# PL-100.net
KiCad netlist of a schematic drawn in EAGLE
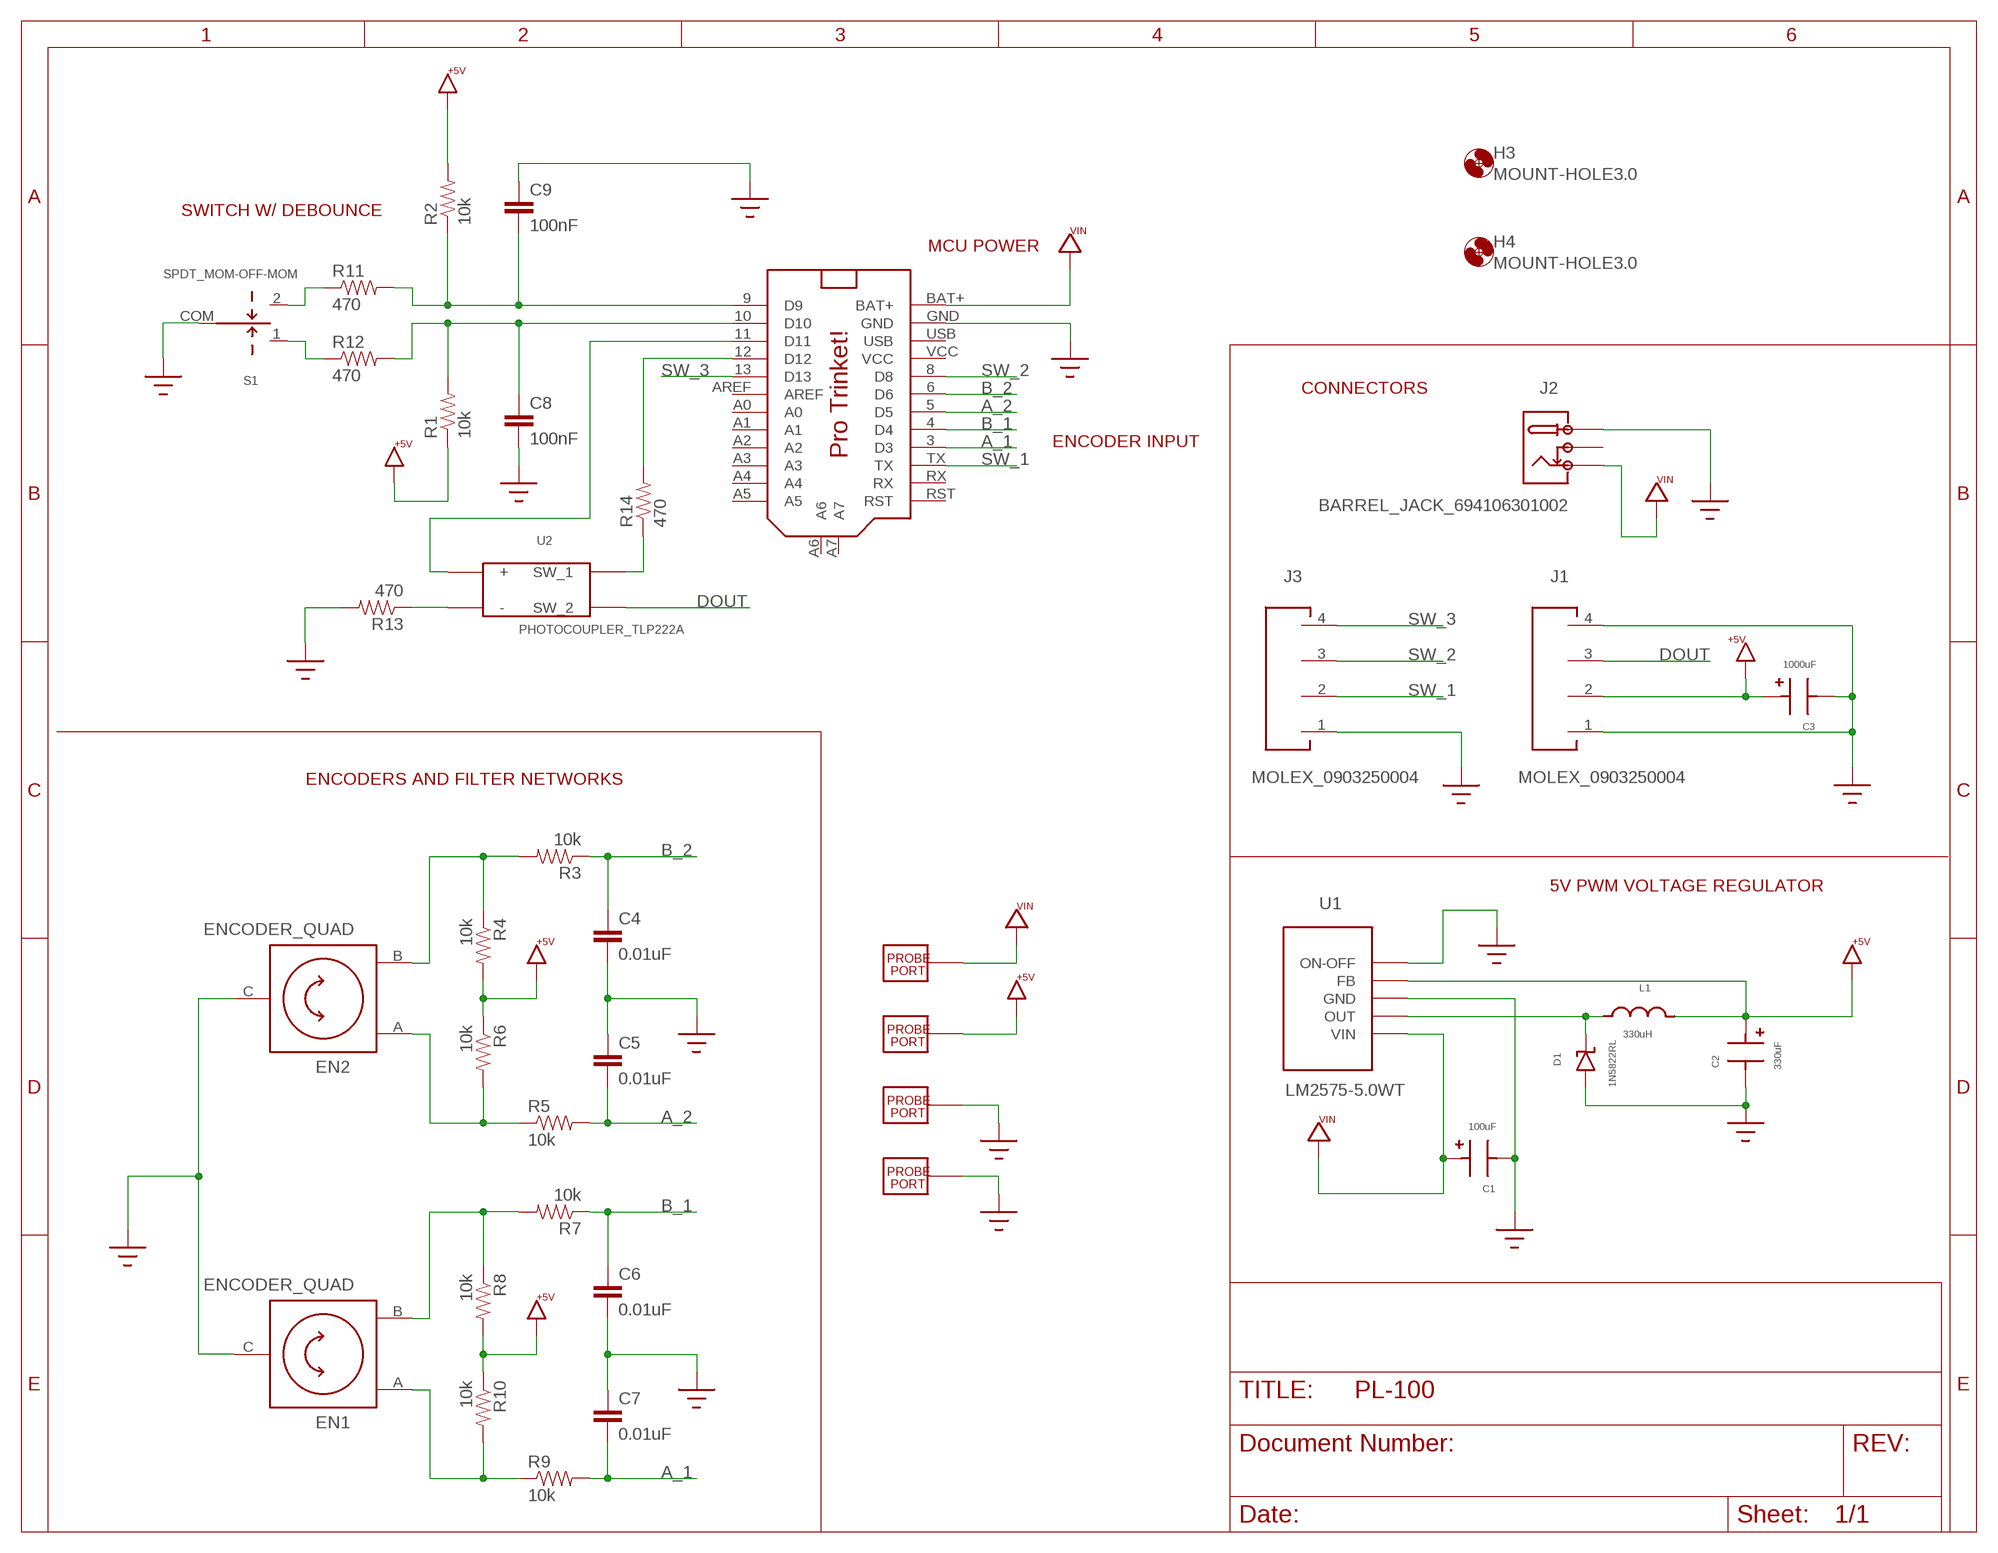
[diagram p0: schematic, sheet 1]

(export (version "E")
  (design (tool "Eeschema 10.0.6"))
  (components
    (comp (ref "+5V")
      (value "PROBE_PORT")
      (footprint "eagle-import:PROBE_PORT")
      (libsource (lib "eagle-import") (part "PROBE_PORT"))
    )
    (comp (ref "C1")
      (value "100uF")
      (footprint "eagle-import:RADIAL_POL_6.3-DIA_2.5-SPACE")
      (libsource (lib "eagle-import") (part "CAP_POL6.3-DIA_2.5-SPACE"))
    )
    (comp (ref "C2")
      (value "330uF")
      (footprint "eagle-import:RADIAL_POL_8-DIA_3.5-SPACE")
      (libsource (lib "eagle-import") (part "CAP_POL8-DIA_3.5-SPACE"))
    )
    (comp (ref "C3")
      (value "1000uF")
      (footprint "eagle-import:RADIAL_POL_10-DIA_5-SPACE")
      (libsource (lib "eagle-import") (part "CAP_POL10-DIA_5-SPACE"))
    )
    (comp (ref "C4")
      (value "0.01uF")
      (footprint "eagle-import:CAP-PTH-SMALLEZ")
      (libsource (lib "eagle-import") (part "CAPEZ"))
    )
    (comp (ref "C5")
      (value "0.01uF")
      (footprint "eagle-import:CAP-PTH-SMALLEZ")
      (libsource (lib "eagle-import") (part "CAPEZ"))
    )
    (comp (ref "C6")
      (value "0.01uF")
      (footprint "eagle-import:CAP-PTH-SMALLEZ")
      (libsource (lib "eagle-import") (part "CAPEZ"))
    )
    (comp (ref "C7")
      (value "0.01uF")
      (footprint "eagle-import:CAP-PTH-SMALLEZ")
      (libsource (lib "eagle-import") (part "CAPEZ"))
    )
    (comp (ref "C8")
      (value "100nF")
      (footprint "eagle-import:CAP-PTH-SMALL")
      (libsource (lib "eagle-import") (part "CAPPTH"))
    )
    (comp (ref "C9")
      (value "100nF")
      (footprint "eagle-import:CAP-PTH-SMALL")
      (libsource (lib "eagle-import") (part "CAPPTH"))
    )
    (comp (ref "D1")
      (value "1N5822RL")
      (footprint "eagle-import:DO-201AD_AXIAL")
      (libsource (lib "eagle-import") (part "DIODE_SHOTTKY"))
    )
    (comp (ref "EN1")
      (value "ENCODER_QUAD")
      (footprint "eagle-import:PEC11R-4015F-N0024")
      (libsource (lib "eagle-import") (part "ENCODER_QUAD"))
    )
    (comp (ref "EN2")
      (value "ENCODER_QUAD")
      (footprint "eagle-import:PEC11R-4015F-N0024")
      (libsource (lib "eagle-import") (part "ENCODER_QUAD"))
    )
    (comp (ref "GND1")
      (value "PROBE_PORT")
      (footprint "eagle-import:PROBE_PORT")
      (libsource (lib "eagle-import") (part "PROBE_PORT"))
    )
    (comp (ref "GND2")
      (value "PROBE_PORT")
      (footprint "eagle-import:PROBE_PORT")
      (libsource (lib "eagle-import") (part "PROBE_PORT"))
    )
    (comp (ref "H3")
      (value "MOUNT-HOLE3.0")
      (footprint "eagle-import:3,0")
      (libsource (lib "eagle-import") (part "MOUNT-HOLE3.0"))
    )
    (comp (ref "H4")
      (value "MOUNT-HOLE3.0")
      (footprint "eagle-import:3,0")
      (libsource (lib "eagle-import") (part "MOUNT-HOLE3.0"))
    )
    (comp (ref "J1")
      (value "MOLEX_0903250004")
      (footprint "eagle-import:0903250004")
      (libsource (lib "eagle-import") (part "MOLEX_0903250004"))
    )
    (comp (ref "J2")
      (value "BARREL_JACK_694106301002")
      (footprint "eagle-import:BARREL_JACK_694106301002")
      (libsource (lib "eagle-import") (part "BARREL_JACK_694106301002"))
    )
    (comp (ref "J3")
      (value "MOLEX_0903250004")
      (footprint "eagle-import:0903250004")
      (libsource (lib "eagle-import") (part "MOLEX_0903250004"))
    )
    (comp (ref "L1")
      (value "330uH")
      (footprint "eagle-import:INDUCT_AXIAL_28-SPACING")
      (libsource (lib "eagle-import") (part "INDUCTOR"))
    )
    (comp (ref "R1")
      (value "10k")
      (footprint "eagle-import:AXIAL-0.4")
      (libsource (lib "eagle-import") (part "RESISTORPTH-1/4W"))
    )
    (comp (ref "R2")
      (value "10k")
      (footprint "eagle-import:AXIAL-0.4")
      (libsource (lib "eagle-import") (part "RESISTORPTH-1/4W"))
    )
    (comp (ref "R3")
      (value "10k")
      (footprint "eagle-import:AXIAL-0.4")
      (libsource (lib "eagle-import") (part "RESISTORPTH-1/4W"))
    )
    (comp (ref "R4")
      (value "10k")
      (footprint "eagle-import:AXIAL-0.4")
      (libsource (lib "eagle-import") (part "RESISTORPTH-1/4W"))
    )
    (comp (ref "R5")
      (value "10k")
      (footprint "eagle-import:AXIAL-0.4")
      (libsource (lib "eagle-import") (part "RESISTORPTH-1/4W"))
    )
    (comp (ref "R6")
      (value "10k")
      (footprint "eagle-import:AXIAL-0.4")
      (libsource (lib "eagle-import") (part "RESISTORPTH-1/4W"))
    )
    (comp (ref "R7")
      (value "10k")
      (footprint "eagle-import:AXIAL-0.4")
      (libsource (lib "eagle-import") (part "RESISTORPTH-1/4W"))
    )
    (comp (ref "R8")
      (value "10k")
      (footprint "eagle-import:AXIAL-0.4")
      (libsource (lib "eagle-import") (part "RESISTORPTH-1/4W"))
    )
    (comp (ref "R9")
      (value "10k")
      (footprint "eagle-import:AXIAL-0.4")
      (libsource (lib "eagle-import") (part "RESISTORPTH-1/4W"))
    )
    (comp (ref "R10")
      (value "10k")
      (footprint "eagle-import:AXIAL-0.4")
      (libsource (lib "eagle-import") (part "RESISTORPTH-1/4W"))
    )
    (comp (ref "R11")
      (value "470")
      (footprint "eagle-import:AXIAL-0.4")
      (libsource (lib "eagle-import") (part "RESISTORPTH-1/4W"))
    )
    (comp (ref "R12")
      (value "470")
      (footprint "eagle-import:AXIAL-0.4")
      (libsource (lib "eagle-import") (part "RESISTORPTH-1/4W"))
    )
    (comp (ref "R13")
      (value "470")
      (footprint "eagle-import:AXIAL-0.4")
      (libsource (lib "eagle-import") (part "RESISTORPTH-1/4W"))
    )
    (comp (ref "R14")
      (value "470")
      (footprint "eagle-import:AXIAL-0.4")
      (libsource (lib "eagle-import") (part "RESISTORPTH-1/4W"))
    )
    (comp (ref "S1")
      (value "SPDT_MOM-OFF-MOM")
      (footprint "eagle-import:100SP4T6B11M2QEH")
      (libsource (lib "eagle-import") (part "SPDT_MOM-OFF-MOM"))
    )
    (comp (ref "U$2")
      (value "PRO_TRINKET")
      (footprint "eagle-import:PROTRINKET")
      (libsource (lib "eagle-import") (part "PRO_TRINKET"))
    )
    (comp (ref "U1")
      (value "LM2575-5.0WT")
      (footprint "eagle-import:TO-220-5")
      (libsource (lib "eagle-import") (part "LM2575-5.0WT"))
    )
    (comp (ref "U2")
      (value "PHOTOCOUPLER_TLP222A")
      (footprint "eagle-import:DIP-4")
      (libsource (lib "eagle-import") (part "PHOTOCOUPLER_TLP222A"))
    )
    (comp (ref "VIN")
      (value "PROBE_PORT")
      (footprint "eagle-import:PROBE_PORT")
      (libsource (lib "eagle-import") (part "PROBE_PORT"))
    )
  )
  (nets
    (net (code "1") (name "+5V") (class "Default")
      (node (ref "+5V") (pin "P$1") (pinfunction "P$1_P$1") (pintype "passive"))
      (node (ref "C2") (pin "+") (pinfunction "+_+") (pintype "passive"))
      (node (ref "C3") (pin "+") (pinfunction "+_+") (pintype "passive"))
      (node (ref "J1") (pin "2") (pinfunction "P$2_2") (pintype "bidirectional"))
      (node (ref "L1") (pin "2") (pinfunction "P$2_2") (pintype "passive"))
      (node (ref "R1") (pin "P$1") (pinfunction "1_P$1") (pintype "passive"))
      (node (ref "R10") (pin "P$1") (pinfunction "1_P$1") (pintype "passive"))
      (node (ref "R2") (pin "P$2") (pinfunction "2_P$2") (pintype "passive"))
      (node (ref "R4") (pin "P$2") (pinfunction "2_P$2") (pintype "passive"))
      (node (ref "R6") (pin "P$1") (pinfunction "1_P$1") (pintype "passive"))
      (node (ref "R8") (pin "P$2") (pinfunction "2_P$2") (pintype "passive"))
      (node (ref "U1") (pin "4") (pinfunction "FB_4") (pintype "input"))
    )
    (net (code "2") (name "/3") (class "Default")
      (node (ref "J2") (pin "3") (pinfunction "3_3") (pintype "power_in"))
    )
    (net (code "3") (name "/A_1") (class "Default")
      (node (ref "C7") (pin "2") (pinfunction "2_2") (pintype "passive"))
      (node (ref "R9") (pin "P$2") (pinfunction "2_P$2") (pintype "passive"))
      (node (ref "U$2") (pin "3") (pinfunction "D3_3") (pintype "bidirectional"))
    )
    (net (code "4") (name "/A_2") (class "Default")
      (node (ref "C5") (pin "2") (pinfunction "2_2") (pintype "passive"))
      (node (ref "R5") (pin "P$2") (pinfunction "2_P$2") (pintype "passive"))
      (node (ref "U$2") (pin "5") (pinfunction "D5_5") (pintype "bidirectional"))
    )
    (net (code "5") (name "/B_1") (class "Default")
      (node (ref "C6") (pin "1") (pinfunction "1_1") (pintype "passive"))
      (node (ref "R7") (pin "P$1") (pinfunction "1_P$1") (pintype "passive"))
      (node (ref "U$2") (pin "4") (pinfunction "D4_4") (pintype "bidirectional"))
    )
    (net (code "6") (name "/B_2") (class "Default")
      (node (ref "C4") (pin "1") (pinfunction "1_1") (pintype "passive"))
      (node (ref "R3") (pin "P$1") (pinfunction "1_P$1") (pintype "passive"))
      (node (ref "U$2") (pin "6") (pinfunction "D6_6") (pintype "bidirectional"))
    )
    (net (code "7") (name "/DOUT") (class "Default")
      (node (ref "J1") (pin "3") (pinfunction "P$3_3") (pintype "passive"))
      (node (ref "U2") (pin "4") (pinfunction "SW_2_4") (pintype "passive"))
    )
    (net (code "8") (name "/SW_1") (class "Default")
      (node (ref "J3") (pin "2") (pinfunction "P$2_2") (pintype "bidirectional"))
      (node (ref "U$2") (pin "TX") (pinfunction "TX_TX") (pintype "bidirectional"))
    )
    (net (code "9") (name "/SW_2") (class "Default")
      (node (ref "J3") (pin "3") (pinfunction "P$3_3") (pintype "passive"))
      (node (ref "U$2") (pin "8") (pinfunction "D8_8") (pintype "bidirectional"))
    )
    (net (code "10") (name "/SW_3") (class "Default")
      (node (ref "J3") (pin "4") (pinfunction "P$4_4") (pintype "passive"))
      (node (ref "U$2") (pin "13") (pinfunction "D13_13") (pintype "bidirectional"))
    )
    (net (code "11") (name "/USB") (class "Default")
      (node (ref "U$2") (pin "USB") (pinfunction "USB_USB") (pintype "power_in"))
    )
    (net (code "12") (name "/VCC") (class "Default")
      (node (ref "U$2") (pin "VCC") (pinfunction "VCC_VCC") (pintype "power_in"))
    )
    (net (code "13") (name "GND") (class "Default")
      (node (ref "C1") (pin "-") (pinfunction "-_-") (pintype "passive"))
      (node (ref "C2") (pin "-") (pinfunction "-_-") (pintype "passive"))
      (node (ref "C3") (pin "-") (pinfunction "-_-") (pintype "passive"))
      (node (ref "C4") (pin "2") (pinfunction "2_2") (pintype "passive"))
      (node (ref "C5") (pin "1") (pinfunction "1_1") (pintype "passive"))
      (node (ref "C6") (pin "2") (pinfunction "2_2") (pintype "passive"))
      (node (ref "C7") (pin "1") (pinfunction "1_1") (pintype "passive"))
      (node (ref "C8") (pin "2") (pinfunction "2_2") (pintype "passive"))
      (node (ref "C9") (pin "1") (pinfunction "1_1") (pintype "passive"))
      (node (ref "D1") (pin "+") (pinfunction "+_+") (pintype "passive"))
      (node (ref "EN1") (pin "C") (pinfunction "2_C") (pintype "output"))
      (node (ref "EN2") (pin "C") (pinfunction "2_C") (pintype "output"))
      (node (ref "GND1") (pin "P$1") (pinfunction "P$1_P$1") (pintype "passive"))
      (node (ref "GND2") (pin "P$1") (pinfunction "P$1_P$1") (pintype "passive"))
      (node (ref "J1") (pin "1") (pinfunction "P$1_1") (pintype "bidirectional"))
      (node (ref "J1") (pin "4") (pinfunction "P$4_4") (pintype "passive"))
      (node (ref "J2") (pin "1") (pinfunction "1_1") (pintype "power_in"))
      (node (ref "J3") (pin "1") (pinfunction "P$1_1") (pintype "bidirectional"))
      (node (ref "R13") (pin "P$2") (pinfunction "2_P$2") (pintype "passive"))
      (node (ref "S1") (pin "COM") (pinfunction "COM_COM") (pintype "passive"))
      (node (ref "U$2") (pin "GND") (pinfunction "GND_GND") (pintype "power_in"))
      (node (ref "U1") (pin "3") (pinfunction "GND_3") (pintype "power_in"))
      (node (ref "U1") (pin "5") (pinfunction "ON-OFF_5") (pintype "input"))
    )
    (net (code "14") (name "Net-(EN1-1)") (class "Default")
      (node (ref "EN1") (pin "A") (pinfunction "1_A") (pintype "output"))
      (node (ref "R10") (pin "P$2") (pinfunction "2_P$2") (pintype "passive"))
      (node (ref "R9") (pin "P$1") (pinfunction "1_P$1") (pintype "passive"))
    )
    (net (code "15") (name "Net-(EN1-3)") (class "Default")
      (node (ref "EN1") (pin "B") (pinfunction "3_B") (pintype "output"))
      (node (ref "R7") (pin "P$2") (pinfunction "2_P$2") (pintype "passive"))
      (node (ref "R8") (pin "P$1") (pinfunction "1_P$1") (pintype "passive"))
    )
    (net (code "16") (name "Net-(EN2-1)") (class "Default")
      (node (ref "EN2") (pin "A") (pinfunction "1_A") (pintype "output"))
      (node (ref "R5") (pin "P$1") (pinfunction "1_P$1") (pintype "passive"))
      (node (ref "R6") (pin "P$2") (pinfunction "2_P$2") (pintype "passive"))
    )
    (net (code "17") (name "Net-(EN2-3)") (class "Default")
      (node (ref "EN2") (pin "B") (pinfunction "3_B") (pintype "output"))
      (node (ref "R3") (pin "P$2") (pinfunction "2_P$2") (pintype "passive"))
      (node (ref "R4") (pin "P$1") (pinfunction "1_P$1") (pintype "passive"))
    )
    (net (code "18") (name "Net-(L1-P$1)") (class "Default")
      (node (ref "D1") (pin "-") (pinfunction "-_-") (pintype "passive"))
      (node (ref "L1") (pin "1") (pinfunction "P$1_1") (pintype "passive"))
      (node (ref "U1") (pin "2") (pinfunction "OUT_2") (pintype "output"))
    )
    (net (code "19") (name "Net-(R1-2)") (class "Default")
      (node (ref "C8") (pin "1") (pinfunction "1_1") (pintype "passive"))
      (node (ref "R1") (pin "P$2") (pinfunction "2_P$2") (pintype "passive"))
      (node (ref "R12") (pin "P$2") (pinfunction "2_P$2") (pintype "passive"))
      (node (ref "U$2") (pin "10") (pinfunction "D10_10") (pintype "bidirectional"))
    )
    (net (code "20") (name "Net-(R11-1)") (class "Default")
      (node (ref "R11") (pin "P$1") (pinfunction "1_P$1") (pintype "passive"))
      (node (ref "S1") (pin "2") (pinfunction "MOM_2_2") (pintype "passive"))
    )
    (net (code "21") (name "Net-(R11-2)") (class "Default")
      (node (ref "C9") (pin "2") (pinfunction "2_2") (pintype "passive"))
      (node (ref "R11") (pin "P$2") (pinfunction "2_P$2") (pintype "passive"))
      (node (ref "R2") (pin "P$1") (pinfunction "1_P$1") (pintype "passive"))
      (node (ref "U$2") (pin "9") (pinfunction "D9_9") (pintype "bidirectional"))
    )
    (net (code "22") (name "Net-(R12-1)") (class "Default")
      (node (ref "R12") (pin "P$1") (pinfunction "1_P$1") (pintype "passive"))
      (node (ref "S1") (pin "1") (pinfunction "MOM_1_1") (pintype "passive"))
    )
    (net (code "23") (name "Net-(R13-1)") (class "Default")
      (node (ref "R13") (pin "P$1") (pinfunction "1_P$1") (pintype "passive"))
      (node (ref "U2") (pin "2") (pinfunction "-_2") (pintype "power_in"))
    )
    (net (code "24") (name "Net-(R14-1)") (class "Default")
      (node (ref "R14") (pin "P$1") (pinfunction "1_P$1") (pintype "passive"))
      (node (ref "U2") (pin "3") (pinfunction "SW_1_3") (pintype "passive"))
    )
    (net (code "25") (name "Net-(R14-2)") (class "Default")
      (node (ref "R14") (pin "P$2") (pinfunction "2_P$2") (pintype "passive"))
      (node (ref "U$2") (pin "12") (pinfunction "D12_12") (pintype "bidirectional"))
    )
    (net (code "26") (name "Net-(U$2-D11)") (class "Default")
      (node (ref "U$2") (pin "11") (pinfunction "D11_11") (pintype "bidirectional"))
      (node (ref "U2") (pin "1") (pinfunction "+_1") (pintype "power_in"))
    )
    (net (code "27") (name "VIN") (class "Default")
      (node (ref "C1") (pin "+") (pinfunction "+_+") (pintype "passive"))
      (node (ref "J2") (pin "2") (pinfunction "2_2") (pintype "power_in"))
      (node (ref "U$2") (pin "BAT+") (pinfunction "BAT+_BAT+") (pintype "power_in"))
      (node (ref "U1") (pin "1") (pinfunction "VIN_1") (pintype "power_in"))
      (node (ref "VIN") (pin "P$1") (pinfunction "P$1_P$1") (pintype "passive"))
    )
    (net (code "28") (name "unconnected-(U$2-PadA0)") (class "Default")
      (node (ref "U$2") (pin "A0") (pinfunction "A0_A0") (pintype "bidirectional"))
    )
    (net (code "29") (name "unconnected-(U$2-PadA1)") (class "Default")
      (node (ref "U$2") (pin "A1") (pinfunction "A1_A1") (pintype "bidirectional"))
    )
    (net (code "30") (name "unconnected-(U$2-PadA2)") (class "Default")
      (node (ref "U$2") (pin "A2") (pinfunction "A2_A2") (pintype "bidirectional"))
    )
    (net (code "31") (name "unconnected-(U$2-PadA3)") (class "Default")
      (node (ref "U$2") (pin "A3") (pinfunction "A3_A3") (pintype "bidirectional"))
    )
    (net (code "32") (name "unconnected-(U$2-PadA4)") (class "Default")
      (node (ref "U$2") (pin "A4") (pinfunction "A4_A4") (pintype "bidirectional"))
    )
    (net (code "33") (name "unconnected-(U$2-PadA5)") (class "Default")
      (node (ref "U$2") (pin "A5") (pinfunction "A5_A5") (pintype "bidirectional"))
    )
    (net (code "34") (name "unconnected-(U$2-PadA6)") (class "Default")
      (node (ref "U$2") (pin "A6") (pinfunction "A6_A6") (pintype "passive"))
    )
    (net (code "35") (name "unconnected-(U$2-PadA7)") (class "Default")
      (node (ref "U$2") (pin "A7") (pinfunction "A7_A7") (pintype "passive"))
    )
    (net (code "36") (name "unconnected-(U$2-PadAREF)") (class "Default")
      (node (ref "U$2") (pin "AREF") (pinfunction "AREF_AREF") (pintype "passive"))
    )
    (net (code "37") (name "unconnected-(U$2-PadRST)") (class "Default")
      (node (ref "U$2") (pin "RST") (pinfunction "RST_RST") (pintype "passive"))
    )
    (net (code "38") (name "unconnected-(U$2-PadRX)") (class "Default")
      (node (ref "U$2") (pin "RX") (pinfunction "RX_RX") (pintype "bidirectional"))
    )
  )
)
